# UltraSonicTestHarnessBoard.net
KiCad netlist of a schematic drawn in Altium Designer
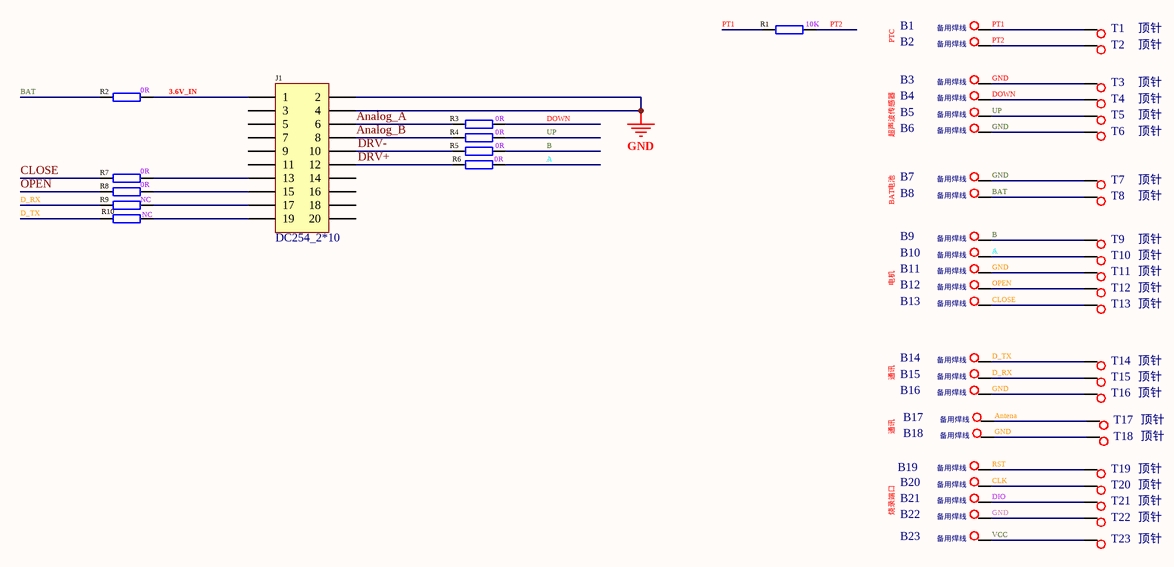
[diagram p0: UltraSonicTestHarnessBoard.SchDoc]

(export (version "E")
  (design (tool "Eeschema 10.0.6"))
  (components
    (comp (ref "B1")
      (value "备用焊线")
      (footprint "Connector:TestPoint")
      (description "通孔测试点")
      (fields (field (name "PART NUMBER") "AD_WXHJ_TEST-POINT_01"))
      (libsource (lib "Database_Libs2") (part "TEST-POINT"))
    )
    (comp (ref "B2")
      (value "备用焊线")
      (footprint "Connector:TestPoint")
      (description "通孔测试点")
      (fields (field (name "PART NUMBER") "AD_WXHJ_TEST-POINT_01"))
      (libsource (lib "Database_Libs2") (part "TEST-POINT"))
    )
    (comp (ref "B3")
      (value "备用焊线")
      (footprint "Connector:TestPoint")
      (description "通孔测试点")
      (fields (field (name "PART NUMBER") "AD_WXHJ_TEST-POINT_01"))
      (libsource (lib "Database_Libs2") (part "TEST-POINT"))
    )
    (comp (ref "B4")
      (value "备用焊线")
      (footprint "Connector:TestPoint")
      (description "通孔测试点")
      (fields (field (name "PART NUMBER") "AD_WXHJ_TEST-POINT_01"))
      (libsource (lib "Database_Libs2") (part "TEST-POINT"))
    )
    (comp (ref "B5")
      (value "备用焊线")
      (footprint "Connector:TestPoint")
      (description "通孔测试点")
      (fields (field (name "PART NUMBER") "AD_WXHJ_TEST-POINT_01"))
      (libsource (lib "Database_Libs2") (part "TEST-POINT"))
    )
    (comp (ref "B6")
      (value "备用焊线")
      (footprint "Connector:TestPoint")
      (description "通孔测试点")
      (fields (field (name "PART NUMBER") "AD_WXHJ_TEST-POINT_01"))
      (libsource (lib "Database_Libs2") (part "TEST-POINT"))
    )
    (comp (ref "B7")
      (value "备用焊线")
      (footprint "Connector:TestPoint")
      (description "通孔测试点")
      (fields (field (name "PART NUMBER") "AD_WXHJ_TEST-POINT_01"))
      (libsource (lib "Database_Libs2") (part "TEST-POINT"))
    )
    (comp (ref "B8")
      (value "备用焊线")
      (footprint "Connector:TestPoint")
      (description "通孔测试点")
      (fields (field (name "PART NUMBER") "AD_WXHJ_TEST-POINT_01"))
      (libsource (lib "Database_Libs2") (part "TEST-POINT"))
    )
    (comp (ref "B9")
      (value "备用焊线")
      (footprint "Connector:TestPoint")
      (description "通孔测试点")
      (fields (field (name "PART NUMBER") "AD_WXHJ_TEST-POINT_01"))
      (libsource (lib "Database_Libs2") (part "TEST-POINT"))
    )
    (comp (ref "B10")
      (value "备用焊线")
      (footprint "Connector:TestPoint")
      (description "通孔测试点")
      (fields (field (name "PART NUMBER") "AD_WXHJ_TEST-POINT_01"))
      (libsource (lib "Database_Libs2") (part "TEST-POINT"))
    )
    (comp (ref "B11")
      (value "备用焊线")
      (footprint "Connector:TestPoint")
      (description "通孔测试点")
      (fields (field (name "PART NUMBER") "AD_WXHJ_TEST-POINT_01"))
      (libsource (lib "Database_Libs2") (part "TEST-POINT"))
    )
    (comp (ref "B12")
      (value "备用焊线")
      (footprint "Connector:TestPoint")
      (description "通孔测试点")
      (fields (field (name "PART NUMBER") "AD_WXHJ_TEST-POINT_01"))
      (libsource (lib "Database_Libs2") (part "TEST-POINT"))
    )
    (comp (ref "B13")
      (value "备用焊线")
      (footprint "Connector:TestPoint")
      (description "通孔测试点")
      (fields (field (name "PART NUMBER") "AD_WXHJ_TEST-POINT_01"))
      (libsource (lib "Database_Libs2") (part "TEST-POINT"))
    )
    (comp (ref "B14")
      (value "备用焊线")
      (footprint "Connector:TestPoint")
      (description "通孔测试点")
      (fields (field (name "PART NUMBER") "AD_WXHJ_TEST-POINT_01"))
      (libsource (lib "Database_Libs2") (part "TEST-POINT"))
    )
    (comp (ref "B15")
      (value "备用焊线")
      (footprint "Connector:TestPoint")
      (description "通孔测试点")
      (fields (field (name "PART NUMBER") "AD_WXHJ_TEST-POINT_01"))
      (libsource (lib "Database_Libs2") (part "TEST-POINT"))
    )
    (comp (ref "B16")
      (value "备用焊线")
      (footprint "Connector:TestPoint")
      (description "通孔测试点")
      (fields (field (name "PART NUMBER") "AD_WXHJ_TEST-POINT_01"))
      (libsource (lib "Database_Libs2") (part "TEST-POINT"))
    )
    (comp (ref "B17")
      (value "备用焊线")
      (footprint "Connector:TestPoint")
      (description "通孔测试点")
      (fields (field (name "PART NUMBER") "AD_WXHJ_TEST-POINT_01"))
      (libsource (lib "Database_Libs2") (part "TEST-POINT"))
    )
    (comp (ref "B18")
      (value "备用焊线")
      (footprint "Connector:TestPoint")
      (description "通孔测试点")
      (fields (field (name "PART NUMBER") "AD_WXHJ_TEST-POINT_01"))
      (libsource (lib "Database_Libs2") (part "TEST-POINT"))
    )
    (comp (ref "B19")
      (value "备用焊线")
      (footprint "Connector:TestPoint")
      (description "通孔测试点")
      (fields (field (name "PART NUMBER") "AD_WXHJ_TEST-POINT_01"))
      (libsource (lib "Database_Libs2") (part "TEST-POINT"))
    )
    (comp (ref "B20")
      (value "备用焊线")
      (footprint "Connector:TestPoint")
      (description "通孔测试点")
      (fields (field (name "PART NUMBER") "AD_WXHJ_TEST-POINT_01"))
      (libsource (lib "Database_Libs2") (part "TEST-POINT"))
    )
    (comp (ref "B21")
      (value "备用焊线")
      (footprint "Connector:TestPoint")
      (description "通孔测试点")
      (fields (field (name "PART NUMBER") "AD_WXHJ_TEST-POINT_01"))
      (libsource (lib "Database_Libs2") (part "TEST-POINT"))
    )
    (comp (ref "B22")
      (value "备用焊线")
      (footprint "Connector:TestPoint")
      (description "通孔测试点")
      (fields (field (name "PART NUMBER") "AD_WXHJ_TEST-POINT_01"))
      (libsource (lib "Database_Libs2") (part "TEST-POINT"))
    )
    (comp (ref "B23")
      (value "备用焊线")
      (footprint "Connector:TestPoint")
      (description "通孔测试点")
      (fields (field (name "PART NUMBER") "AD_WXHJ_TEST-POINT_01"))
      (libsource (lib "Database_Libs2") (part "TEST-POINT"))
    )
    (comp (ref "J1")
      (value "DC254_2*10")
      (footprint "Connector:IDC2.54-LI-2x10P")
      (description "DC2 2.54mm 2x10pin,2.54mm间距，2x10pin，32×8.55×27.5mm,母头,双排,双排牛角座")
      (fields (field (name "PART NUMBER") "1010902-0139"))
      (libsource (lib "Database_Libs2") (part "DC254_2*10"))
    )
    (comp (ref "R1")
      (value "10K")
      (footprint "Resistor:R-1206")
      (description "0Ω,±5%,1/4W,1206,国巨,RC1206JR-070RL")
      (fields (field (name "PART NUMBER") "101010101-0013"))
      (libsource (lib "Database_Libs2") (part "RC06J_0R"))
    )
    (comp (ref "R2")
      (value "0R")
      (footprint "Resistor:R-1206")
      (description "0Ω,±5%,1/4W,1206,国巨,RC1206JR-070RL")
      (fields (field (name "PART NUMBER") "101010101-0013"))
      (libsource (lib "Database_Libs2") (part "RC06J_0R"))
    )
    (comp (ref "R3")
      (value "0R")
      (footprint "Resistor:R-1206")
      (description "0Ω,±5%,1/4W,1206,国巨,RC1206JR-070RL")
      (fields (field (name "PART NUMBER") "101010101-0013"))
      (libsource (lib "Database_Libs2") (part "RC06J_0R"))
    )
    (comp (ref "R4")
      (value "0R")
      (footprint "Resistor:R-1206")
      (description "0Ω,±5%,1/4W,1206,国巨,RC1206JR-070RL")
      (fields (field (name "PART NUMBER") "101010101-0013"))
      (libsource (lib "Database_Libs2") (part "RC06J_0R"))
    )
    (comp (ref "R5")
      (value "0R")
      (footprint "Resistor:R-1206")
      (description "0Ω,±5%,1/4W,1206,国巨,RC1206JR-070RL")
      (fields (field (name "PART NUMBER") "101010101-0013"))
      (libsource (lib "Database_Libs2") (part "RC06J_0R"))
    )
    (comp (ref "R6")
      (value "0R")
      (footprint "Resistor:R-1206")
      (description "0Ω,±5%,1/4W,1206,国巨,RC1206JR-070RL")
      (fields (field (name "PART NUMBER") "101010101-0013"))
      (libsource (lib "Database_Libs2") (part "RC06J_0R"))
    )
    (comp (ref "R7")
      (value "0R")
      (footprint "Resistor:R-1206")
      (description "0Ω,±5%,1/4W,1206,国巨,RC1206JR-070RL")
      (fields (field (name "PART NUMBER") "101010101-0013"))
      (libsource (lib "Database_Libs2") (part "RC06J_0R"))
    )
    (comp (ref "R8")
      (value "0R")
      (footprint "Resistor:R-1206")
      (description "0Ω,±5%,1/4W,1206,国巨,RC1206JR-070RL")
      (fields (field (name "PART NUMBER") "101010101-0013"))
      (libsource (lib "Database_Libs2") (part "RC06J_0R"))
    )
    (comp (ref "R9")
      (value "NC")
      (footprint "Resistor:R-1206")
      (description "0Ω,±5%,1/4W,1206,国巨,RC1206JR-070RL")
      (fields (field (name "PART NUMBER") "101010101-0013"))
      (libsource (lib "Database_Libs2") (part "RC06J_0R"))
    )
    (comp (ref "R10")
      (value "NC")
      (footprint "Resistor:R-1206")
      (description "0Ω,±5%,1/4W,1206,国巨,RC1206JR-070RL")
      (fields (field (name "PART NUMBER") "101010101-0013"))
      (libsource (lib "Database_Libs2") (part "RC06J_0R"))
    )
    (comp (ref "T1")
      (value "顶针")
      (footprint "Connector:TestPoint")
      (description "通孔测试点")
      (fields (field (name "PART NUMBER") "AD_WXHJ_TEST-POINT_01"))
      (libsource (lib "Database_Libs2") (part "TEST-POINT"))
    )
    (comp (ref "T2")
      (value "顶针")
      (footprint "Connector:TestPoint")
      (description "通孔测试点")
      (fields (field (name "PART NUMBER") "AD_WXHJ_TEST-POINT_01"))
      (libsource (lib "Database_Libs2") (part "TEST-POINT"))
    )
    (comp (ref "T3")
      (value "顶针")
      (footprint "Connector:TestPoint")
      (description "通孔测试点")
      (fields (field (name "PART NUMBER") "AD_WXHJ_TEST-POINT_01"))
      (libsource (lib "Database_Libs2") (part "TEST-POINT"))
    )
    (comp (ref "T4")
      (value "顶针")
      (footprint "Connector:TestPoint")
      (description "通孔测试点")
      (fields (field (name "PART NUMBER") "AD_WXHJ_TEST-POINT_01"))
      (libsource (lib "Database_Libs2") (part "TEST-POINT"))
    )
    (comp (ref "T5")
      (value "顶针")
      (footprint "Connector:TestPoint")
      (description "通孔测试点")
      (fields (field (name "PART NUMBER") "AD_WXHJ_TEST-POINT_01"))
      (libsource (lib "Database_Libs2") (part "TEST-POINT"))
    )
    (comp (ref "T6")
      (value "顶针")
      (footprint "Connector:TestPoint")
      (description "通孔测试点")
      (fields (field (name "PART NUMBER") "AD_WXHJ_TEST-POINT_01"))
      (libsource (lib "Database_Libs2") (part "TEST-POINT"))
    )
    (comp (ref "T7")
      (value "顶针")
      (footprint "Connector:TestPoint")
      (description "通孔测试点")
      (fields (field (name "PART NUMBER") "AD_WXHJ_TEST-POINT_01"))
      (libsource (lib "Database_Libs2") (part "TEST-POINT"))
    )
    (comp (ref "T8")
      (value "顶针")
      (footprint "Connector:TestPoint")
      (description "通孔测试点")
      (fields (field (name "PART NUMBER") "AD_WXHJ_TEST-POINT_01"))
      (libsource (lib "Database_Libs2") (part "TEST-POINT"))
    )
    (comp (ref "T9")
      (value "顶针")
      (footprint "Connector:TestPoint")
      (description "通孔测试点")
      (fields (field (name "PART NUMBER") "AD_WXHJ_TEST-POINT_01"))
      (libsource (lib "Database_Libs2") (part "TEST-POINT"))
    )
    (comp (ref "T10")
      (value "顶针")
      (footprint "Connector:TestPoint")
      (description "通孔测试点")
      (fields (field (name "PART NUMBER") "AD_WXHJ_TEST-POINT_01"))
      (libsource (lib "Database_Libs2") (part "TEST-POINT"))
    )
    (comp (ref "T11")
      (value "顶针")
      (footprint "Connector:TestPoint")
      (description "通孔测试点")
      (fields (field (name "PART NUMBER") "AD_WXHJ_TEST-POINT_01"))
      (libsource (lib "Database_Libs2") (part "TEST-POINT"))
    )
    (comp (ref "T12")
      (value "顶针")
      (footprint "Connector:TestPoint")
      (description "通孔测试点")
      (fields (field (name "PART NUMBER") "AD_WXHJ_TEST-POINT_01"))
      (libsource (lib "Database_Libs2") (part "TEST-POINT"))
    )
    (comp (ref "T13")
      (value "顶针")
      (footprint "Connector:TestPoint")
      (description "通孔测试点")
      (fields (field (name "PART NUMBER") "AD_WXHJ_TEST-POINT_01"))
      (libsource (lib "Database_Libs2") (part "TEST-POINT"))
    )
    (comp (ref "T14")
      (value "顶针")
      (footprint "Connector:TestPoint")
      (description "通孔测试点")
      (fields (field (name "PART NUMBER") "AD_WXHJ_TEST-POINT_01"))
      (libsource (lib "Database_Libs2") (part "TEST-POINT"))
    )
    (comp (ref "T15")
      (value "顶针")
      (footprint "Connector:TestPoint")
      (description "通孔测试点")
      (fields (field (name "PART NUMBER") "AD_WXHJ_TEST-POINT_01"))
      (libsource (lib "Database_Libs2") (part "TEST-POINT"))
    )
    (comp (ref "T16")
      (value "顶针")
      (footprint "Connector:TestPoint")
      (description "通孔测试点")
      (fields (field (name "PART NUMBER") "AD_WXHJ_TEST-POINT_01"))
      (libsource (lib "Database_Libs2") (part "TEST-POINT"))
    )
    (comp (ref "T17")
      (value "顶针")
      (footprint "Connector:TestPoint")
      (description "通孔测试点")
      (fields (field (name "PART NUMBER") "AD_WXHJ_TEST-POINT_01"))
      (libsource (lib "Database_Libs2") (part "TEST-POINT"))
    )
    (comp (ref "T18")
      (value "顶针")
      (footprint "Connector:TestPoint")
      (description "通孔测试点")
      (fields (field (name "PART NUMBER") "AD_WXHJ_TEST-POINT_01"))
      (libsource (lib "Database_Libs2") (part "TEST-POINT"))
    )
    (comp (ref "T19")
      (value "顶针")
      (footprint "Connector:TestPoint")
      (description "通孔测试点")
      (fields (field (name "PART NUMBER") "AD_WXHJ_TEST-POINT_01"))
      (libsource (lib "Database_Libs2") (part "TEST-POINT"))
    )
    (comp (ref "T20")
      (value "顶针")
      (footprint "Connector:TestPoint")
      (description "通孔测试点")
      (fields (field (name "PART NUMBER") "AD_WXHJ_TEST-POINT_01"))
      (libsource (lib "Database_Libs2") (part "TEST-POINT"))
    )
    (comp (ref "T21")
      (value "顶针")
      (footprint "Connector:TestPoint")
      (description "通孔测试点")
      (fields (field (name "PART NUMBER") "AD_WXHJ_TEST-POINT_01"))
      (libsource (lib "Database_Libs2") (part "TEST-POINT"))
    )
    (comp (ref "T22")
      (value "顶针")
      (footprint "Connector:TestPoint")
      (description "通孔测试点")
      (fields (field (name "PART NUMBER") "AD_WXHJ_TEST-POINT_01"))
      (libsource (lib "Database_Libs2") (part "TEST-POINT"))
    )
    (comp (ref "T23")
      (value "顶针")
      (footprint "Connector:TestPoint")
      (description "通孔测试点")
      (fields (field (name "PART NUMBER") "AD_WXHJ_TEST-POINT_01"))
      (libsource (lib "Database_Libs2") (part "TEST-POINT"))
    )
  )
  (nets
    (net (code "1") (name "/3.6V_IN") (class "Default")
      (node (ref "J1") (pin "1") (pinfunction "1_1") (pintype "passive"))
      (node (ref "R2") (pin "2") (pinfunction "2_2") (pintype "passive"))
    )
    (net (code "2") (name "/A") (class "Default")
      (node (ref "B10") (pin "1") (pinfunction "1_1") (pintype "passive"))
      (node (ref "R6") (pin "1") (pinfunction "1_1") (pintype "passive"))
      (node (ref "T10") (pin "1") (pinfunction "1_1") (pintype "passive"))
    )
    (net (code "3") (name "/Analog_A") (class "Default")
      (node (ref "J1") (pin "6") (pinfunction "6_6") (pintype "passive"))
      (node (ref "R3") (pin "2") (pinfunction "2_2") (pintype "passive"))
    )
    (net (code "4") (name "/Analog_B") (class "Default")
      (node (ref "J1") (pin "8") (pinfunction "8_8") (pintype "passive"))
      (node (ref "R4") (pin "2") (pinfunction "2_2") (pintype "passive"))
    )
    (net (code "5") (name "/Antena") (class "Default")
      (node (ref "B17") (pin "1") (pinfunction "1_1") (pintype "passive"))
      (node (ref "T17") (pin "1") (pinfunction "1_1") (pintype "passive"))
    )
    (net (code "6") (name "/B") (class "Default")
      (node (ref "B9") (pin "1") (pinfunction "1_1") (pintype "passive"))
      (node (ref "R5") (pin "1") (pinfunction "1_1") (pintype "passive"))
      (node (ref "T9") (pin "1") (pinfunction "1_1") (pintype "passive"))
    )
    (net (code "7") (name "/BAT") (class "Default")
      (node (ref "B8") (pin "1") (pinfunction "1_1") (pintype "passive"))
      (node (ref "R2") (pin "1") (pinfunction "1_1") (pintype "passive"))
      (node (ref "T8") (pin "1") (pinfunction "1_1") (pintype "passive"))
    )
    (net (code "8") (name "/CLK") (class "Default")
      (node (ref "B20") (pin "1") (pinfunction "1_1") (pintype "passive"))
      (node (ref "T20") (pin "1") (pinfunction "1_1") (pintype "passive"))
    )
    (net (code "9") (name "/CLOSE") (class "Default")
      (node (ref "B13") (pin "1") (pinfunction "1_1") (pintype "passive"))
      (node (ref "R7") (pin "1") (pinfunction "1_1") (pintype "passive"))
      (node (ref "T13") (pin "1") (pinfunction "1_1") (pintype "passive"))
    )
    (net (code "10") (name "/DIO") (class "Default")
      (node (ref "B21") (pin "1") (pinfunction "1_1") (pintype "passive"))
      (node (ref "T21") (pin "1") (pinfunction "1_1") (pintype "passive"))
    )
    (net (code "11") (name "/DOWN") (class "Default")
      (node (ref "B4") (pin "1") (pinfunction "1_1") (pintype "passive"))
      (node (ref "R3") (pin "1") (pinfunction "1_1") (pintype "passive"))
      (node (ref "T4") (pin "1") (pinfunction "1_1") (pintype "passive"))
    )
    (net (code "12") (name "/DRV+") (class "Default")
      (node (ref "J1") (pin "12") (pinfunction "12_12") (pintype "passive"))
      (node (ref "R6") (pin "2") (pinfunction "2_2") (pintype "passive"))
    )
    (net (code "13") (name "/DRV-") (class "Default")
      (node (ref "J1") (pin "10") (pinfunction "10_10") (pintype "passive"))
      (node (ref "R5") (pin "2") (pinfunction "2_2") (pintype "passive"))
    )
    (net (code "14") (name "/D_RX") (class "Default")
      (node (ref "B15") (pin "1") (pinfunction "1_1") (pintype "passive"))
      (node (ref "R9") (pin "1") (pinfunction "1_1") (pintype "passive"))
      (node (ref "T15") (pin "1") (pinfunction "1_1") (pintype "passive"))
    )
    (net (code "15") (name "/D_TX") (class "Default")
      (node (ref "B14") (pin "1") (pinfunction "1_1") (pintype "passive"))
      (node (ref "R10") (pin "1") (pinfunction "1_1") (pintype "passive"))
      (node (ref "T14") (pin "1") (pinfunction "1_1") (pintype "passive"))
    )
    (net (code "16") (name "/OPEN") (class "Default")
      (node (ref "B12") (pin "1") (pinfunction "1_1") (pintype "passive"))
      (node (ref "R8") (pin "1") (pinfunction "1_1") (pintype "passive"))
      (node (ref "T12") (pin "1") (pinfunction "1_1") (pintype "passive"))
    )
    (net (code "17") (name "/PT1") (class "Default")
      (node (ref "B1") (pin "1") (pinfunction "1_1") (pintype "passive"))
      (node (ref "R1") (pin "2") (pinfunction "2_2") (pintype "passive"))
      (node (ref "T1") (pin "1") (pinfunction "1_1") (pintype "passive"))
    )
    (net (code "18") (name "/PT2") (class "Default")
      (node (ref "B2") (pin "1") (pinfunction "1_1") (pintype "passive"))
      (node (ref "R1") (pin "1") (pinfunction "1_1") (pintype "passive"))
      (node (ref "T2") (pin "1") (pinfunction "1_1") (pintype "passive"))
    )
    (net (code "19") (name "/RST") (class "Default")
      (node (ref "B19") (pin "1") (pinfunction "1_1") (pintype "passive"))
      (node (ref "T19") (pin "1") (pinfunction "1_1") (pintype "passive"))
    )
    (net (code "20") (name "/UP") (class "Default")
      (node (ref "B5") (pin "1") (pinfunction "1_1") (pintype "passive"))
      (node (ref "R4") (pin "1") (pinfunction "1_1") (pintype "passive"))
      (node (ref "T5") (pin "1") (pinfunction "1_1") (pintype "passive"))
    )
    (net (code "21") (name "/VCC") (class "Default")
      (node (ref "B23") (pin "1") (pinfunction "1_1") (pintype "passive"))
      (node (ref "T23") (pin "1") (pinfunction "1_1") (pintype "passive"))
    )
    (net (code "22") (name "GND") (class "Default")
      (node (ref "B11") (pin "1") (pinfunction "1_1") (pintype "passive"))
      (node (ref "B16") (pin "1") (pinfunction "1_1") (pintype "passive"))
      (node (ref "B18") (pin "1") (pinfunction "1_1") (pintype "passive"))
      (node (ref "B22") (pin "1") (pinfunction "1_1") (pintype "passive"))
      (node (ref "B3") (pin "1") (pinfunction "1_1") (pintype "passive"))
      (node (ref "B6") (pin "1") (pinfunction "1_1") (pintype "passive"))
      (node (ref "B7") (pin "1") (pinfunction "1_1") (pintype "passive"))
      (node (ref "J1") (pin "2") (pinfunction "2_2") (pintype "passive"))
      (node (ref "J1") (pin "4") (pinfunction "4_4") (pintype "passive"))
      (node (ref "T11") (pin "1") (pinfunction "1_1") (pintype "passive"))
      (node (ref "T16") (pin "1") (pinfunction "1_1") (pintype "passive"))
      (node (ref "T18") (pin "1") (pinfunction "1_1") (pintype "passive"))
      (node (ref "T22") (pin "1") (pinfunction "1_1") (pintype "passive"))
      (node (ref "T3") (pin "1") (pinfunction "1_1") (pintype "passive"))
      (node (ref "T6") (pin "1") (pinfunction "1_1") (pintype "passive"))
      (node (ref "T7") (pin "1") (pinfunction "1_1") (pintype "passive"))
    )
    (net (code "23") (name "Net-(J1-Pad13)") (class "Default")
      (node (ref "J1") (pin "13") (pinfunction "13_13") (pintype "passive"))
      (node (ref "R7") (pin "2") (pinfunction "2_2") (pintype "passive"))
    )
    (net (code "24") (name "Net-(J1-Pad15)") (class "Default")
      (node (ref "J1") (pin "15") (pinfunction "15_15") (pintype "passive"))
      (node (ref "R8") (pin "2") (pinfunction "2_2") (pintype "passive"))
    )
    (net (code "25") (name "Net-(J1-Pad17)") (class "Default")
      (node (ref "J1") (pin "17") (pinfunction "17_17") (pintype "passive"))
      (node (ref "R9") (pin "2") (pinfunction "2_2") (pintype "passive"))
    )
    (net (code "26") (name "Net-(J1-Pad19)") (class "Default")
      (node (ref "J1") (pin "19") (pinfunction "19_19") (pintype "passive"))
      (node (ref "R10") (pin "2") (pinfunction "2_2") (pintype "passive"))
    )
    (net (code "27") (name "unconnected-(J1-Pad3)") (class "Default")
      (node (ref "J1") (pin "3") (pinfunction "3_3") (pintype "passive"))
    )
    (net (code "28") (name "unconnected-(J1-Pad5)") (class "Default")
      (node (ref "J1") (pin "5") (pinfunction "5_5") (pintype "passive"))
    )
    (net (code "29") (name "unconnected-(J1-Pad7)") (class "Default")
      (node (ref "J1") (pin "7") (pinfunction "7_7") (pintype "passive"))
    )
    (net (code "30") (name "unconnected-(J1-Pad9)") (class "Default")
      (node (ref "J1") (pin "9") (pinfunction "9_9") (pintype "passive"))
    )
    (net (code "31") (name "unconnected-(J1-Pad11)") (class "Default")
      (node (ref "J1") (pin "11") (pinfunction "11_11") (pintype "passive"))
    )
    (net (code "32") (name "unconnected-(J1-Pad14)") (class "Default")
      (node (ref "J1") (pin "14") (pinfunction "14_14") (pintype "passive"))
    )
    (net (code "33") (name "unconnected-(J1-Pad16)") (class "Default")
      (node (ref "J1") (pin "16") (pinfunction "16_16") (pintype "passive"))
    )
    (net (code "34") (name "unconnected-(J1-Pad18)") (class "Default")
      (node (ref "J1") (pin "18") (pinfunction "18_18") (pintype "passive"))
    )
    (net (code "35") (name "unconnected-(J1-Pad20)") (class "Default")
      (node (ref "J1") (pin "20") (pinfunction "20_20") (pintype "passive"))
    )
  )
)
